# untitled.net
KiCad netlist of a schematic drawn in EAGLE
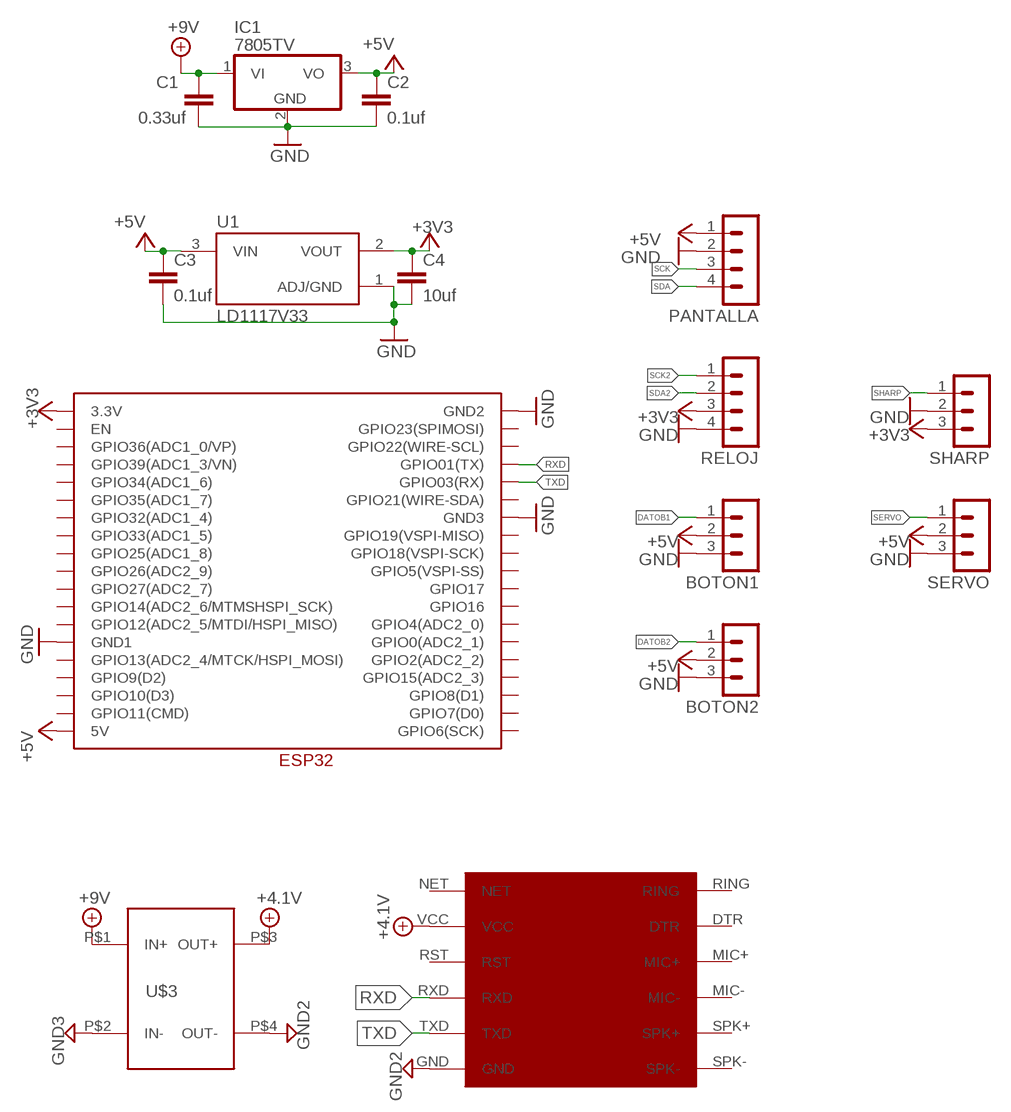
[diagram p0: schematic, sheet 1]

(export (version "E")
  (design (tool "Eeschema 10.0.6"))
  (components
    (comp (ref "BOTON1")
      (value "MA03-1")
      (footprint "eagle-import:MA03-1")
      (libsource (lib "eagle-import") (part "MA03-1"))
    )
    (comp (ref "BOTON2")
      (value "MA03-1")
      (footprint "eagle-import:MA03-1")
      (libsource (lib "eagle-import") (part "MA03-1"))
    )
    (comp (ref "C1")
      (value "0.33uf")
      (footprint "eagle-import:C2.5-3")
      (libsource (lib "eagle-import") (part "C2,5-3"))
    )
    (comp (ref "C2")
      (value "0.1uf")
      (footprint "eagle-import:C2.5-3")
      (libsource (lib "eagle-import") (part "C2,5-3"))
    )
    (comp (ref "C3")
      (value "0.1uf")
      (footprint "eagle-import:C2.5-3")
      (libsource (lib "eagle-import") (part "C2,5-3"))
    )
    (comp (ref "C4")
      (value "10uf")
      (footprint "eagle-import:C2.5-3")
      (libsource (lib "eagle-import") (part "C2,5-3"))
    )
    (comp (ref "IC1")
      (value "7805TV")
      (footprint "eagle-import:TO220V")
      (libsource (lib "eagle-import") (part "78TV05"))
    )
    (comp (ref "PANTALLA")
      (value "MA04-1")
      (footprint "eagle-import:MA04-1")
      (libsource (lib "eagle-import") (part "MA04-1"))
    )
    (comp (ref "RELOJ")
      (value "MA04-1")
      (footprint "eagle-import:MA04-1")
      (libsource (lib "eagle-import") (part "MA04-1"))
    )
    (comp (ref "SERVO")
      (value "MA03-1")
      (footprint "eagle-import:MA03-1")
      (libsource (lib "eagle-import") (part "MA03-1"))
    )
    (comp (ref "SHARP")
      (value "MA03-1")
      (footprint "eagle-import:MA03-1")
      (libsource (lib "eagle-import") (part "MA03-1"))
    )
    (comp (ref "U$1")
      (value "ESP32WESP32W")
      (footprint "eagle-import:ESP32W")
      (libsource (lib "eagle-import") (part "ESP32WESP32W"))
    )
    (comp (ref "U$2")
      (value "SIM800L")
      (footprint "eagle-import:SIM800L")
      (libsource (lib "eagle-import") (part "SIM800L"))
    )
    (comp (ref "U$3")
      (value "XL6009E1")
      (footprint "eagle-import:XL6009E1")
      (libsource (lib "eagle-import") (part "XL6009E1"))
    )
    (comp (ref "U1")
      (value "LD1117V33")
      (footprint "eagle-import:TO255P1020X450X1968-3")
      (fields (field (name "MF") "STMicroelectronics"))
      (libsource (lib "eagle-import") (part "LD1117V33"))
    )
  )
  (nets
    (net (code "1") (name "+3V3") (class "Default")
      (node (ref "C4") (pin "1") (pinfunction "1_1") (pintype "passive"))
      (node (ref "RELOJ") (pin "3") (pinfunction "3_3") (pintype "passive"))
      (node (ref "SHARP") (pin "3") (pinfunction "3_3") (pintype "passive"))
      (node (ref "U$1") (pin "3.3V") (pinfunction "3.3V_3.3V") (pintype "bidirectional"))
      (node (ref "U1") (pin "2") (pinfunction "VOUT_2") (pintype "output"))
    )
    (net (code "2") (name "+4.1V") (class "Default")
      (node (ref "U$2") (pin "VCC") (pinfunction "VCC_VCC") (pintype "bidirectional"))
      (node (ref "U$3") (pin "P$3") (pinfunction "OUT+_P$3") (pintype "bidirectional"))
    )
    (net (code "3") (name "+5V") (class "Default")
      (node (ref "BOTON1") (pin "2") (pinfunction "2_2") (pintype "passive"))
      (node (ref "BOTON2") (pin "2") (pinfunction "2_2") (pintype "passive"))
      (node (ref "C2") (pin "1") (pinfunction "1_1") (pintype "passive"))
      (node (ref "C3") (pin "1") (pinfunction "1_1") (pintype "passive"))
      (node (ref "IC1") (pin "3") (pinfunction "VO_3") (pintype "passive"))
      (node (ref "PANTALLA") (pin "1") (pinfunction "1_1") (pintype "passive"))
      (node (ref "SERVO") (pin "2") (pinfunction "2_2") (pintype "passive"))
      (node (ref "U$1") (pin "5V") (pinfunction "5V_5V") (pintype "bidirectional"))
      (node (ref "U1") (pin "3") (pinfunction "VIN_3") (pintype "input"))
    )
    (net (code "4") (name "+9V") (class "Default")
      (node (ref "C1") (pin "1") (pinfunction "1_1") (pintype "passive"))
      (node (ref "IC1") (pin "1") (pinfunction "VI_1") (pintype "input"))
      (node (ref "U$3") (pin "P$1") (pinfunction "IN+_P$1") (pintype "bidirectional"))
    )
    (net (code "5") (name "DATOB1") (class "Default")
      (node (ref "BOTON1") (pin "1") (pinfunction "1_1") (pintype "passive"))
    )
    (net (code "6") (name "DATOB2") (class "Default")
      (node (ref "BOTON2") (pin "1") (pinfunction "1_1") (pintype "passive"))
    )
    (net (code "7") (name "GND") (class "Default")
      (node (ref "BOTON1") (pin "3") (pinfunction "3_3") (pintype "passive"))
      (node (ref "BOTON2") (pin "3") (pinfunction "3_3") (pintype "passive"))
      (node (ref "C1") (pin "2") (pinfunction "2_2") (pintype "passive"))
      (node (ref "C2") (pin "2") (pinfunction "2_2") (pintype "passive"))
      (node (ref "C3") (pin "2") (pinfunction "2_2") (pintype "passive"))
      (node (ref "C4") (pin "2") (pinfunction "2_2") (pintype "passive"))
      (node (ref "IC1") (pin "2") (pinfunction "GND_2") (pintype "passive"))
      (node (ref "PANTALLA") (pin "2") (pinfunction "2_2") (pintype "passive"))
      (node (ref "RELOJ") (pin "4") (pinfunction "4_4") (pintype "passive"))
      (node (ref "SERVO") (pin "3") (pinfunction "3_3") (pintype "passive"))
      (node (ref "SHARP") (pin "2") (pinfunction "2_2") (pintype "passive"))
      (node (ref "U$1") (pin "GND1") (pinfunction "GND1_GND1") (pintype "bidirectional"))
      (node (ref "U$1") (pin "GND2") (pinfunction "GND2_GND2") (pintype "bidirectional"))
      (node (ref "U$1") (pin "GND3") (pinfunction "GND3_GND3") (pintype "bidirectional"))
      (node (ref "U1") (pin "1") (pinfunction "ADJ/GND_1") (pintype "passive"))
    )
    (net (code "8") (name "GND2") (class "Default")
      (node (ref "U$2") (pin "GND") (pinfunction "GND_GND") (pintype "bidirectional"))
      (node (ref "U$3") (pin "P$4") (pinfunction "OUT-_P$4") (pintype "bidirectional"))
    )
    (net (code "9") (name "GND3") (class "Default")
      (node (ref "U$3") (pin "P$2") (pinfunction "IN-_P$2") (pintype "bidirectional"))
    )
    (net (code "10") (name "RXD") (class "Default")
      (node (ref "U$1") (pin "TX") (pinfunction "GPIO01(TX)_TX") (pintype "bidirectional"))
      (node (ref "U$2") (pin "RXD") (pinfunction "RXD_RXD") (pintype "bidirectional"))
    )
    (net (code "11") (name "SCK") (class "Default")
      (node (ref "PANTALLA") (pin "3") (pinfunction "3_3") (pintype "passive"))
    )
    (net (code "12") (name "SCK2") (class "Default")
      (node (ref "RELOJ") (pin "1") (pinfunction "1_1") (pintype "passive"))
    )
    (net (code "13") (name "SDA") (class "Default")
      (node (ref "PANTALLA") (pin "4") (pinfunction "4_4") (pintype "passive"))
    )
    (net (code "14") (name "SDA2") (class "Default")
      (node (ref "RELOJ") (pin "2") (pinfunction "2_2") (pintype "passive"))
    )
    (net (code "15") (name "SERVO") (class "Default")
      (node (ref "SERVO") (pin "1") (pinfunction "1_1") (pintype "passive"))
    )
    (net (code "16") (name "SHARP") (class "Default")
      (node (ref "SHARP") (pin "1") (pinfunction "1_1") (pintype "passive"))
    )
    (net (code "17") (name "TXD") (class "Default")
      (node (ref "U$1") (pin "RX") (pinfunction "GPIO03(RX)_RX") (pintype "bidirectional"))
      (node (ref "U$2") (pin "TXD") (pinfunction "TXD_TXD") (pintype "bidirectional"))
    )
    (net (code "18") (name "unconnected-(U$1-GPIO0(ADC2_1)-PadGPIO0)") (class "Default")
      (node (ref "U$1") (pin "GPIO0") (pinfunction "GPIO0(ADC2_1)_GPIO0") (pintype "bidirectional"))
    )
    (net (code "19") (name "unconnected-(U$1-GPIO2(ADC2_2)-PadGPIO2)") (class "Default")
      (node (ref "U$1") (pin "GPIO2") (pinfunction "GPIO2(ADC2_2)_GPIO2") (pintype "bidirectional"))
    )
    (net (code "20") (name "unconnected-(U$1-GPIO4(ADC2_0)-PadGPIO4)") (class "Default")
      (node (ref "U$1") (pin "GPIO4") (pinfunction "GPIO4(ADC2_0)_GPIO4") (pintype "bidirectional"))
    )
    (net (code "21") (name "unconnected-(U$1-GPIO5(VSPI-SS)-PadGPIO5)") (class "Default")
      (node (ref "U$1") (pin "GPIO5") (pinfunction "GPIO5(VSPI-SS)_GPIO5") (pintype "bidirectional"))
    )
    (net (code "22") (name "unconnected-(U$1-GPIO6(SCK)-PadCLK)") (class "Default")
      (node (ref "U$1") (pin "CLK") (pinfunction "GPIO6(SCK)_CLK") (pintype "bidirectional"))
    )
    (net (code "23") (name "unconnected-(U$1-GPIO7(D0)-PadSDO)") (class "Default")
      (node (ref "U$1") (pin "SDO") (pinfunction "GPIO7(D0)_SDO") (pintype "bidirectional"))
    )
    (net (code "24") (name "unconnected-(U$1-GPIO8(D1)-PadSDI)") (class "Default")
      (node (ref "U$1") (pin "SDI") (pinfunction "GPIO8(D1)_SDI") (pintype "bidirectional"))
    )
    (net (code "25") (name "unconnected-(U$1-GPIO9(D2)-PadD2)") (class "Default")
      (node (ref "U$1") (pin "D2") (pinfunction "GPIO9(D2)_D2") (pintype "bidirectional"))
    )
    (net (code "26") (name "unconnected-(U$1-GPIO10(D3)-PadD3)") (class "Default")
      (node (ref "U$1") (pin "D3") (pinfunction "GPIO10(D3)_D3") (pintype "bidirectional"))
    )
    (net (code "27") (name "unconnected-(U$1-GPIO11(CMD)-PadCMD)") (class "Default")
      (node (ref "U$1") (pin "CMD") (pinfunction "GPIO11(CMD)_CMD") (pintype "bidirectional"))
    )
    (net (code "28") (name "unconnected-(U$1-GPIO12(ADC2_5{slash}MTDI{slash}HSPI_MISO)-PadGPIO12)") (class "Default")
      (node (ref "U$1") (pin "GPIO12") (pinfunction "GPIO12(ADC2_5/MTDI/HSPI_MISO)_GPIO12") (pintype "bidirectional"))
    )
    (net (code "29") (name "unconnected-(U$1-GPIO13(ADC2_4{slash}MTCK{slash}HSPI_MOSI)-PadGPIO13)") (class "Default")
      (node (ref "U$1") (pin "GPIO13") (pinfunction "GPIO13(ADC2_4/MTCK/HSPI_MOSI)_GPIO13") (pintype "bidirectional"))
    )
    (net (code "30") (name "unconnected-(U$1-GPIO14(ADC2_6{slash}MTMSHSPI_SCK)-PadGPIO14)") (class "Default")
      (node (ref "U$1") (pin "GPIO14") (pinfunction "GPIO14(ADC2_6/MTMSHSPI_SCK)_GPIO14") (pintype "bidirectional"))
    )
    (net (code "31") (name "unconnected-(U$1-GPIO15(ADC2_3)-PadGPIO15)") (class "Default")
      (node (ref "U$1") (pin "GPIO15") (pinfunction "GPIO15(ADC2_3)_GPIO15") (pintype "bidirectional"))
    )
    (net (code "32") (name "unconnected-(U$1-GPIO18(VSPI-SCK)-PadGPIO18)") (class "Default")
      (node (ref "U$1") (pin "GPIO18") (pinfunction "GPIO18(VSPI-SCK)_GPIO18") (pintype "bidirectional"))
    )
    (net (code "33") (name "unconnected-(U$1-GPIO19(VSPI-MISO)-PadGPIO19)") (class "Default")
      (node (ref "U$1") (pin "GPIO19") (pinfunction "GPIO19(VSPI-MISO)_GPIO19") (pintype "bidirectional"))
    )
    (net (code "34") (name "unconnected-(U$1-GPIO21(WIRE-SDA)-PadGPIO21)") (class "Default")
      (node (ref "U$1") (pin "GPIO21") (pinfunction "GPIO21(WIRE-SDA)_GPIO21") (pintype "bidirectional"))
    )
    (net (code "35") (name "unconnected-(U$1-GPIO22(WIRE-SCL)-PadGPIO22)") (class "Default")
      (node (ref "U$1") (pin "GPIO22") (pinfunction "GPIO22(WIRE-SCL)_GPIO22") (pintype "bidirectional"))
    )
    (net (code "36") (name "unconnected-(U$1-GPIO23(SPIMOSI)-PadGPIO23)") (class "Default")
      (node (ref "U$1") (pin "GPIO23") (pinfunction "GPIO23(SPIMOSI)_GPIO23") (pintype "bidirectional"))
    )
    (net (code "37") (name "unconnected-(U$1-GPIO25(ADC1_8)-PadGPIO25)") (class "Default")
      (node (ref "U$1") (pin "GPIO25") (pinfunction "GPIO25(ADC1_8)_GPIO25") (pintype "bidirectional"))
    )
    (net (code "38") (name "unconnected-(U$1-GPIO26(ADC2_9)-PadGPIO26)") (class "Default")
      (node (ref "U$1") (pin "GPIO26") (pinfunction "GPIO26(ADC2_9)_GPIO26") (pintype "bidirectional"))
    )
    (net (code "39") (name "unconnected-(U$1-GPIO27(ADC2_7)-PadGPIO27)") (class "Default")
      (node (ref "U$1") (pin "GPIO27") (pinfunction "GPIO27(ADC2_7)_GPIO27") (pintype "bidirectional"))
    )
    (net (code "40") (name "unconnected-(U$1-GPIO32(ADC1_4)-PadGPIO32)") (class "Default")
      (node (ref "U$1") (pin "GPIO32") (pinfunction "GPIO32(ADC1_4)_GPIO32") (pintype "bidirectional"))
    )
    (net (code "41") (name "unconnected-(U$1-GPIO33(ADC1_5)-PadGPIO33)") (class "Default")
      (node (ref "U$1") (pin "GPIO33") (pinfunction "GPIO33(ADC1_5)_GPIO33") (pintype "bidirectional"))
    )
    (net (code "42") (name "unconnected-(U$1-GPIO34(ADC1_6)-PadGPIO34)") (class "Default")
      (node (ref "U$1") (pin "GPIO34") (pinfunction "GPIO34(ADC1_6)_GPIO34") (pintype "bidirectional"))
    )
    (net (code "43") (name "unconnected-(U$1-GPIO35(ADC1_7)-PadGPIO35)") (class "Default")
      (node (ref "U$1") (pin "GPIO35") (pinfunction "GPIO35(ADC1_7)_GPIO35") (pintype "bidirectional"))
    )
    (net (code "44") (name "unconnected-(U$1-GPIO36(ADC1_0{slash}VP)-PadVP)") (class "Default")
      (node (ref "U$1") (pin "VP") (pinfunction "GPIO36(ADC1_0/VP)_VP") (pintype "bidirectional"))
    )
    (net (code "45") (name "unconnected-(U$1-GPIO39(ADC1_3{slash}VN)-PadVN)") (class "Default")
      (node (ref "U$1") (pin "VN") (pinfunction "GPIO39(ADC1_3/VN)_VN") (pintype "bidirectional"))
    )
    (net (code "46") (name "unconnected-(U$1-PadEN)") (class "Default")
      (node (ref "U$1") (pin "EN") (pinfunction "EN_EN") (pintype "bidirectional"))
    )
    (net (code "47") (name "unconnected-(U$1-PadGPIO16)") (class "Default")
      (node (ref "U$1") (pin "GPIO16") (pinfunction "GPIO16_GPIO16") (pintype "bidirectional"))
    )
    (net (code "48") (name "unconnected-(U$1-PadGPIO17)") (class "Default")
      (node (ref "U$1") (pin "GPIO17") (pinfunction "GPIO17_GPIO17") (pintype "bidirectional"))
    )
    (net (code "49") (name "unconnected-(U$2-PadDTR)") (class "Default")
      (node (ref "U$2") (pin "DTR") (pinfunction "DTR_DTR") (pintype "bidirectional"))
    )
    (net (code "50") (name "unconnected-(U$2-PadMIC+)") (class "Default")
      (node (ref "U$2") (pin "MIC+") (pinfunction "MIC+_MIC+") (pintype "bidirectional"))
    )
    (net (code "51") (name "unconnected-(U$2-PadMIC-)") (class "Default")
      (node (ref "U$2") (pin "MIC-") (pinfunction "MIC-_MIC-") (pintype "bidirectional"))
    )
    (net (code "52") (name "unconnected-(U$2-PadNET)") (class "Default")
      (node (ref "U$2") (pin "NET") (pinfunction "NET_NET") (pintype "bidirectional"))
    )
    (net (code "53") (name "unconnected-(U$2-PadRING)") (class "Default")
      (node (ref "U$2") (pin "RING") (pinfunction "RING_RING") (pintype "bidirectional"))
    )
    (net (code "54") (name "unconnected-(U$2-PadRST)") (class "Default")
      (node (ref "U$2") (pin "RST") (pinfunction "RST_RST") (pintype "bidirectional"))
    )
    (net (code "55") (name "unconnected-(U$2-PadSPK+)") (class "Default")
      (node (ref "U$2") (pin "SPK+") (pinfunction "SPK+_SPK+") (pintype "bidirectional"))
    )
    (net (code "56") (name "unconnected-(U$2-PadSPK-)") (class "Default")
      (node (ref "U$2") (pin "SPK-") (pinfunction "SPK-_SPK-") (pintype "bidirectional"))
    )
  )
)
